# EVGP_Daugherboard_2.net
KiCad netlist of a schematic drawn in EAGLE
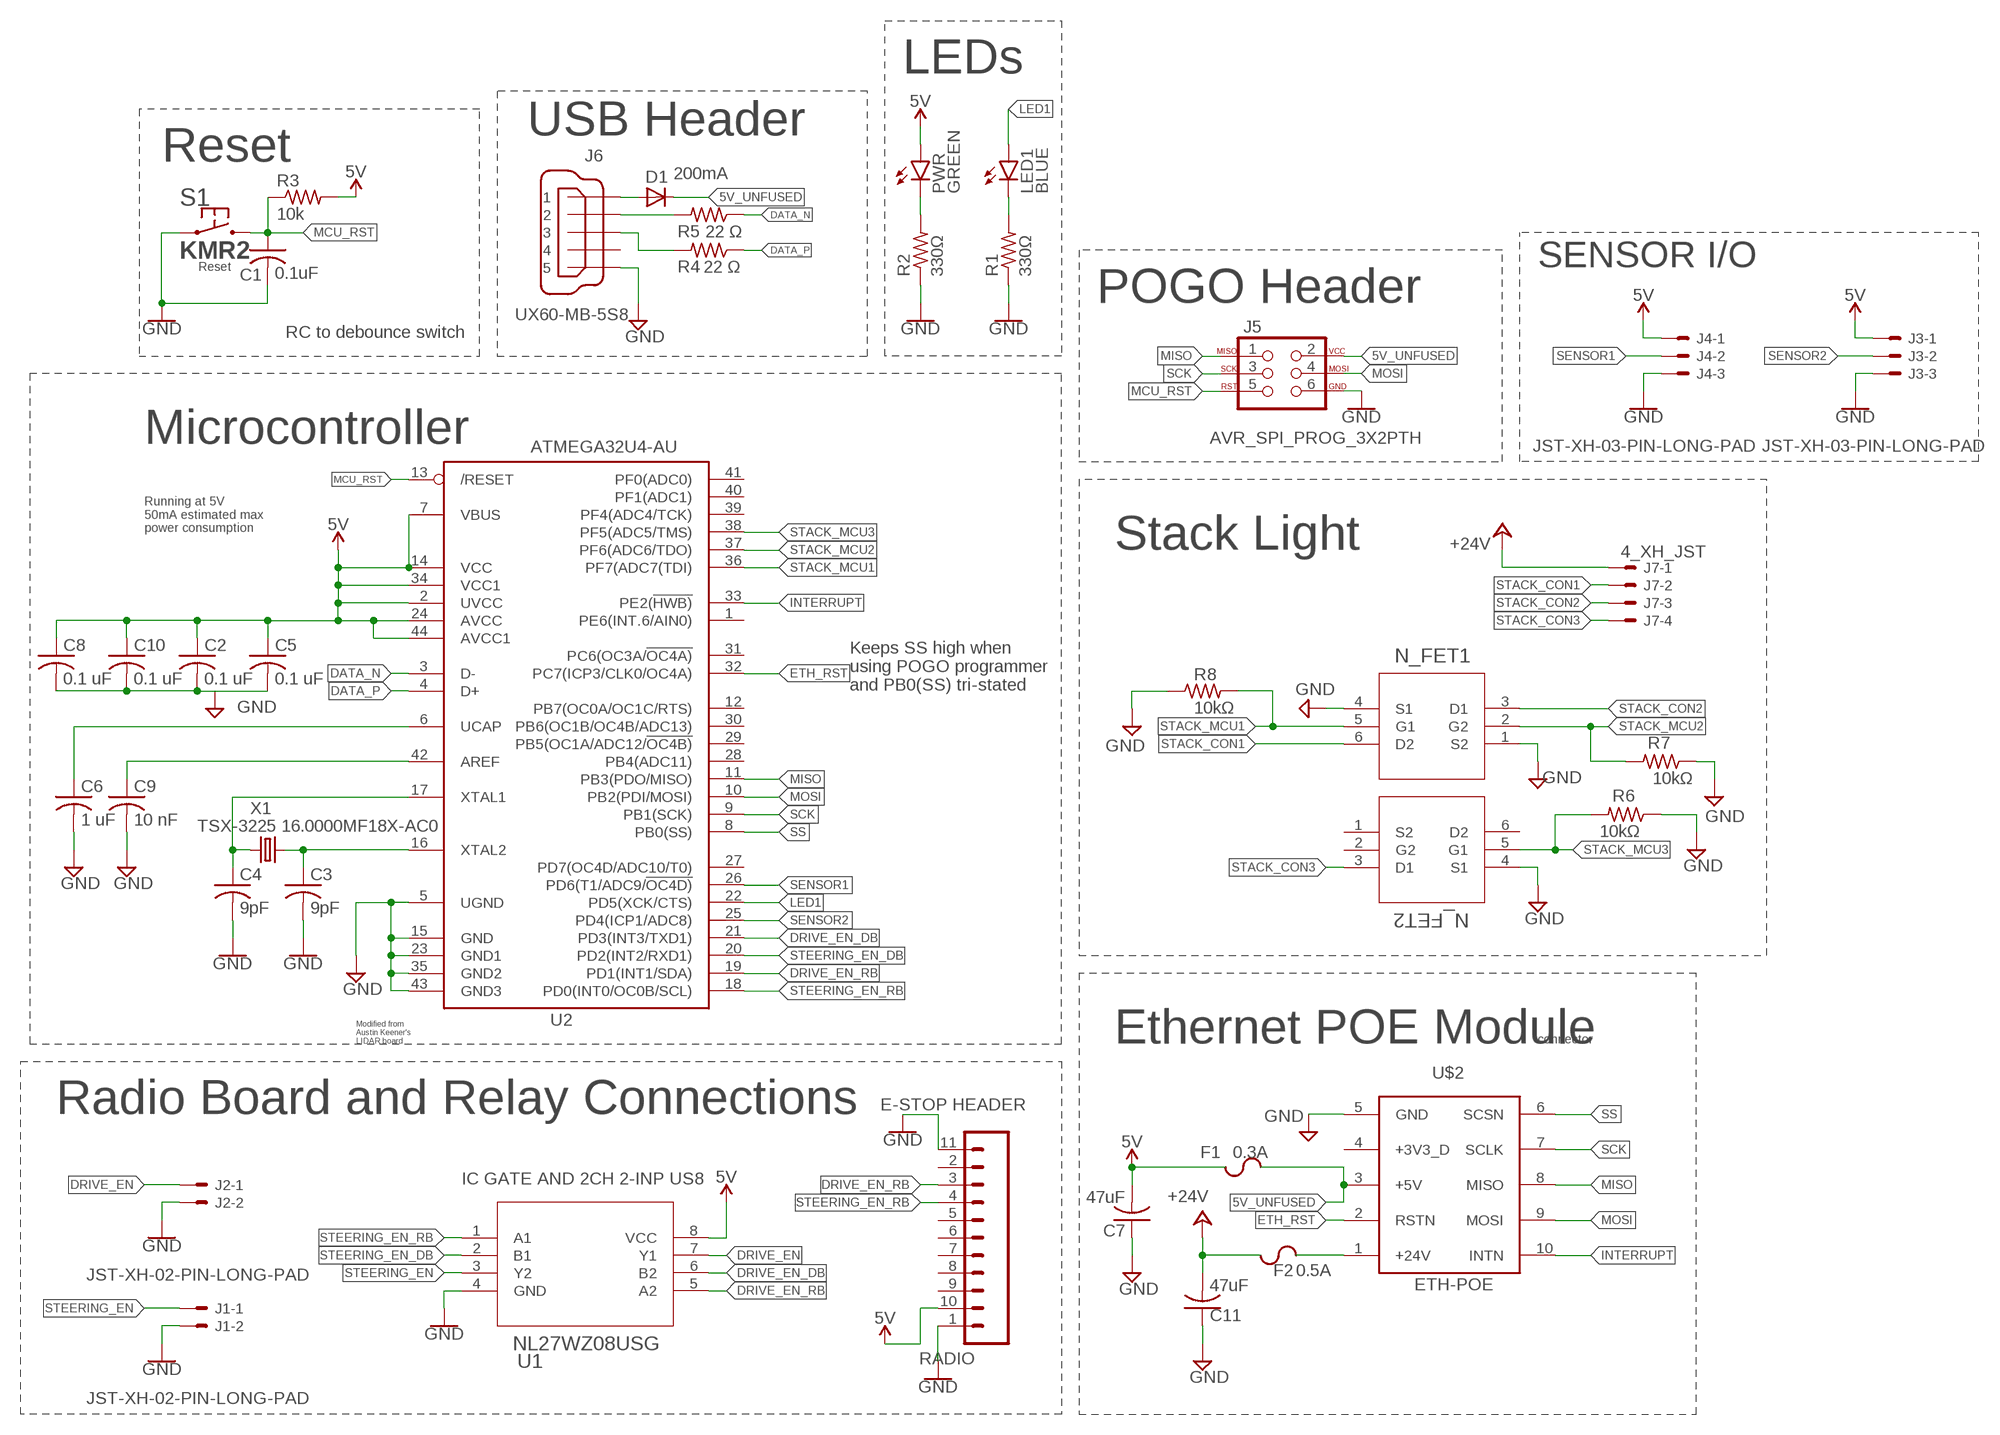
[diagram p0: schematic, sheet 1]

(export (version "E")
  (design (tool "Eeschema 10.0.6"))
  (components
    (comp (ref "C1")
      (value "0.1uF")
      (footprint "eagle-import:C0603")
      (libsource (lib "eagle-import") (part "C-USC0603"))
    )
    (comp (ref "C2")
      (value "0.1 uF")
      (footprint "eagle-import:C0603")
      (libsource (lib "eagle-import") (part "resistor_348_C-USC0603"))
    )
    (comp (ref "C3")
      (value "9pF")
      (footprint "eagle-import:C0603")
      (libsource (lib "eagle-import") (part "resistor_348_C-USC0603"))
    )
    (comp (ref "C4")
      (value "9pF")
      (footprint "eagle-import:C0603")
      (libsource (lib "eagle-import") (part "resistor_348_C-USC0603"))
    )
    (comp (ref "C5")
      (value "0.1 uF")
      (footprint "eagle-import:C0603")
      (libsource (lib "eagle-import") (part "resistor_348_C-USC0603"))
    )
    (comp (ref "C6")
      (value "1 uF")
      (footprint "eagle-import:C0603")
      (libsource (lib "eagle-import") (part "resistor_348_C-USC0603"))
    )
    (comp (ref "C7")
      (value "47uF")
      (footprint "eagle-import:C1206")
      (libsource (lib "eagle-import") (part "C-USC1206"))
    )
    (comp (ref "C8")
      (value "0.1 uF")
      (footprint "eagle-import:C0603")
      (libsource (lib "eagle-import") (part "resistor_348_C-USC0603"))
    )
    (comp (ref "C9")
      (value "10 nF")
      (footprint "eagle-import:C0603")
      (libsource (lib "eagle-import") (part "resistor_348_C-USC0603"))
    )
    (comp (ref "C10")
      (value "0.1 uF")
      (footprint "eagle-import:C0603")
      (libsource (lib "eagle-import") (part "resistor_348_C-USC0603"))
    )
    (comp (ref "C11")
      (value "47uF")
      (footprint "eagle-import:C1206")
      (libsource (lib "eagle-import") (part "C-USC1206"))
    )
    (comp (ref "D1")
      (value "200mA")
      (footprint "eagle-import:SOD323-R")
      (libsource (lib "eagle-import") (part "DIODE-SOD323-R"))
    )
    (comp (ref "F1")
      (value "0.3A")
      (footprint "eagle-import:F1206")
      (libsource (lib "eagle-import") (part "CHIP_FUSE1206"))
    )
    (comp (ref "F2")
      (value "0.5A")
      (footprint "eagle-import:F1206")
      (libsource (lib "eagle-import") (part "CHIP_FUSE1206"))
    )
    (comp (ref "J1")
      (value "JST-XH-02-PIN-LONG-PAD")
      (footprint "eagle-import:JST-XH-02-PACKAGE-LONG-PAD")
      (libsource (lib "eagle-import") (part "JST-XH-02-PIN-LONG-PAD"))
    )
    (comp (ref "J2")
      (value "JST-XH-02-PIN-LONG-PAD")
      (footprint "eagle-import:JST-XH-02-PACKAGE-LONG-PAD")
      (libsource (lib "eagle-import") (part "JST-XH-02-PIN-LONG-PAD"))
    )
    (comp (ref "J3")
      (value "JST-XH-03-PIN-LONG-PAD")
      (footprint "eagle-import:JST-XH-03-PACKAGE-LONG-PAD")
      (libsource (lib "eagle-import") (part "JST-XH-03-PIN-LONG-PAD"))
    )
    (comp (ref "J4")
      (value "JST-XH-03-PIN-LONG-PAD")
      (footprint "eagle-import:JST-XH-03-PACKAGE-LONG-PAD")
      (libsource (lib "eagle-import") (part "JST-XH-03-PIN-LONG-PAD"))
    )
    (comp (ref "J5")
      (value "AVR_SPI_PROG_3X2PTH")
      (footprint "eagle-import:2X3")
      (libsource (lib "eagle-import") (part "AVR_SPI_PROG_3X2PTH"))
    )
    (comp (ref "J6")
      (value "UX60-MB-5S8")
      (footprint "eagle-import:UX60-MB-5S8")
      (libsource (lib "eagle-import") (part "UX60-MB-5S?8"))
    )
    (comp (ref "J7")
      (value "4_XH_JST")
      (footprint "eagle-import:JST-XH-04-PACKAGE-LONG-PAD")
      (libsource (lib "eagle-import") (part "JST-XH-04-PIN-LONG-PAD"))
    )
    (comp (ref "LED1")
      (value "BLUE")
      (footprint "eagle-import:CHIP-LED0603")
      (libsource (lib "eagle-import") (part "LEDCHIP-LED0603"))
    )
    (comp (ref "PWR")
      (value "GREEN")
      (footprint "eagle-import:CHIP-LED0603")
      (libsource (lib "eagle-import") (part "LEDCHIP-LED0603"))
    )
    (comp (ref "Q1")
      (value "N_FET2")
      (footprint "eagle-import:SOT-363")
      (fields (field (name "MANUFACTURER_PART_NUMBER") "BSS84DW7F"))
      (libsource (lib "eagle-import") (part "BSS84DW-7-F"))
    )
    (comp (ref "Q2")
      (value "N_FET1")
      (footprint "eagle-import:SOT-363")
      (fields (field (name "MANUFACTURER_PART_NUMBER") "BSS84DW7F"))
      (libsource (lib "eagle-import") (part "BSS84DW-7-F"))
    )
    (comp (ref "R1")
      (value "330Ω")
      (footprint "eagle-import:R0603")
      (libsource (lib "eagle-import") (part "R-US_R0603"))
    )
    (comp (ref "R2")
      (value "330Ω")
      (footprint "eagle-import:R0603")
      (libsource (lib "eagle-import") (part "R-US_R0603"))
    )
    (comp (ref "R3")
      (value "10k")
      (footprint "eagle-import:R0603")
      (libsource (lib "eagle-import") (part "R-US_R0603"))
    )
    (comp (ref "R4")
      (value "22 Ω")
      (footprint "eagle-import:R0603")
      (libsource (lib "eagle-import") (part "R-US_R0603"))
    )
    (comp (ref "R5")
      (value "22 Ω")
      (footprint "eagle-import:R0603")
      (libsource (lib "eagle-import") (part "R-US_R0603"))
    )
    (comp (ref "R6")
      (value "10kΩ")
      (footprint "eagle-import:R0603")
      (libsource (lib "eagle-import") (part "R-US_R0603"))
    )
    (comp (ref "R7")
      (value "10kΩ")
      (footprint "eagle-import:R0603")
      (libsource (lib "eagle-import") (part "R-US_R0603"))
    )
    (comp (ref "R8")
      (value "10kΩ")
      (footprint "eagle-import:R0603")
      (libsource (lib "eagle-import") (part "R-US_R0603"))
    )
    (comp (ref "RADIO")
      (value "E-STOP HEADER")
      (footprint "eagle-import:RADIO_V1.3")
      (libsource (lib "eagle-import") (part "ESTOP_RADIO"))
    )
    (comp (ref "S1")
      (value "KMR2")
      (footprint "eagle-import:KMR2")
      (fields (field (name "FUNCTION") "Reset"))
      (libsource (lib "eagle-import") (part "KMR2"))
    )
    (comp (ref "U$2")
      (value "ETH-POE")
      (footprint "eagle-import:HDRVR10W64P4000X254_2X5_1016X508X254B")
      (libsource (lib "eagle-import") (part "ETH-POE"))
    )
    (comp (ref "U1")
      (value "NL27WZ08USG")
      (footprint "eagle-import:US8_2P40X2P10")
      (libsource (lib "eagle-import") (part "NL27WZ08USG"))
    )
    (comp (ref "U2")
      (value "ATMEGA32U4-AU")
      (footprint "eagle-import:TQFP44")
      (libsource (lib "eagle-import") (part "ATMEGA32U4-AU"))
    )
    (comp (ref "X1")
      (value "TSX-3225 16.0000MF18X-AC0")
      (footprint "eagle-import:XTAL-3.2X2.5")
      (libsource (lib "eagle-import") (part "XTAL-3.2X2.5"))
    )
  )
  (nets
    (net (code "1") (name "+24V") (class "Default")
      (node (ref "C11") (pin "2") (pinfunction "2_2") (pintype "passive"))
      (node (ref "F2") (pin "1") (pinfunction "1_1") (pintype "bidirectional"))
      (node (ref "J7") (pin "1") (pinfunction "S_1") (pintype "passive"))
    )
    (net (code "2") (name "5V") (class "Default")
      (node (ref "C10") (pin "1") (pinfunction "1_1") (pintype "passive"))
      (node (ref "C2") (pin "1") (pinfunction "1_1") (pintype "passive"))
      (node (ref "C5") (pin "1") (pinfunction "1_1") (pintype "passive"))
      (node (ref "C7") (pin "2") (pinfunction "2_2") (pintype "passive"))
      (node (ref "C8") (pin "1") (pinfunction "1_1") (pintype "passive"))
      (node (ref "F1") (pin "1") (pinfunction "1_1") (pintype "bidirectional"))
      (node (ref "J3") (pin "1") (pinfunction "S_1") (pintype "passive"))
      (node (ref "J4") (pin "1") (pinfunction "S_1") (pintype "passive"))
      (node (ref "PWR") (pin "A") (pinfunction "A_A") (pintype "passive"))
      (node (ref "R3") (pin "2") (pinfunction "2_2") (pintype "passive"))
      (node (ref "RADIO") (pin "10") (pinfunction "5V_10") (pintype "passive"))
      (node (ref "U1") (pin "8") (pinfunction "VCC_8") (pintype "power_in"))
      (node (ref "U2") (pin "14") (pinfunction "VCC_14") (pintype "bidirectional"))
      (node (ref "U2") (pin "2") (pinfunction "UVCC_2") (pintype "bidirectional"))
      (node (ref "U2") (pin "24") (pinfunction "AVCC_24") (pintype "bidirectional"))
      (node (ref "U2") (pin "34") (pinfunction "VCC1_34") (pintype "bidirectional"))
      (node (ref "U2") (pin "44") (pinfunction "AVCC1_44") (pintype "bidirectional"))
      (node (ref "U2") (pin "7") (pinfunction "VBUS_7") (pintype "bidirectional"))
    )
    (net (code "3") (name "5V_UNFUSED") (class "Default")
      (node (ref "D1") (pin "C") (pinfunction "C_C") (pintype "passive"))
      (node (ref "F1") (pin "2") (pinfunction "2_2") (pintype "bidirectional"))
      (node (ref "J5") (pin "2") (pinfunction "2_2") (pintype "passive"))
      (node (ref "U$2") (pin "3") (pinfunction "+5V_3") (pintype "bidirectional"))
    )
    (net (code "4") (name "DATA_N") (class "Default")
      (node (ref "R5") (pin "1") (pinfunction "1_1") (pintype "passive"))
      (node (ref "U2") (pin "3") (pinfunction "D-_3") (pintype "bidirectional"))
    )
    (net (code "5") (name "DATA_P") (class "Default")
      (node (ref "R4") (pin "1") (pinfunction "1_1") (pintype "passive"))
      (node (ref "U2") (pin "4") (pinfunction "D+_4") (pintype "bidirectional"))
    )
    (net (code "6") (name "DRIVE_EN") (class "Default")
      (node (ref "J2") (pin "1") (pinfunction "S_1") (pintype "passive"))
      (node (ref "U1") (pin "7") (pinfunction "Y1_7") (pintype "output"))
    )
    (net (code "7") (name "DRIVE_EN_DB") (class "Default")
      (node (ref "U1") (pin "6") (pinfunction "B2_6") (pintype "input"))
      (node (ref "U2") (pin "21") (pinfunction "PD3(INT3/TXD1)_21") (pintype "bidirectional"))
    )
    (net (code "8") (name "DRIVE_EN_RB") (class "Default")
      (node (ref "RADIO") (pin "3") (pinfunction "D1_3") (pintype "passive"))
      (node (ref "U1") (pin "5") (pinfunction "A2_5") (pintype "input"))
      (node (ref "U2") (pin "19") (pinfunction "PD1(INT1/SDA)_19") (pintype "bidirectional"))
    )
    (net (code "9") (name "ETH_RST") (class "Default")
      (node (ref "U$2") (pin "2") (pinfunction "RSTN_2") (pintype "bidirectional"))
      (node (ref "U2") (pin "32") (pinfunction "PC7(ICP3/CLK0/OC4A)_32") (pintype "bidirectional"))
    )
    (net (code "10") (name "GND") (class "Default")
      (node (ref "C1") (pin "2") (pinfunction "2_2") (pintype "passive"))
      (node (ref "C10") (pin "2") (pinfunction "2_2") (pintype "passive"))
      (node (ref "C11") (pin "1") (pinfunction "1_1") (pintype "passive"))
      (node (ref "C2") (pin "2") (pinfunction "2_2") (pintype "passive"))
      (node (ref "C3") (pin "2") (pinfunction "2_2") (pintype "passive"))
      (node (ref "C4") (pin "2") (pinfunction "2_2") (pintype "passive"))
      (node (ref "C5") (pin "2") (pinfunction "2_2") (pintype "passive"))
      (node (ref "C6") (pin "2") (pinfunction "2_2") (pintype "passive"))
      (node (ref "C7") (pin "1") (pinfunction "1_1") (pintype "passive"))
      (node (ref "C8") (pin "2") (pinfunction "2_2") (pintype "passive"))
      (node (ref "C9") (pin "2") (pinfunction "2_2") (pintype "passive"))
      (node (ref "J1") (pin "2") (pinfunction "S_2") (pintype "passive"))
      (node (ref "J2") (pin "2") (pinfunction "S_2") (pintype "passive"))
      (node (ref "J3") (pin "3") (pinfunction "S_3") (pintype "passive"))
      (node (ref "J4") (pin "3") (pinfunction "S_3") (pintype "passive"))
      (node (ref "J5") (pin "6") (pinfunction "6_6") (pintype "passive"))
      (node (ref "J6") (pin "5") (pinfunction "5_5") (pintype "passive"))
      (node (ref "Q1") (pin "4") (pinfunction "S1_4") (pintype "passive"))
      (node (ref "Q2") (pin "1") (pinfunction "S2_1") (pintype "passive"))
      (node (ref "Q2") (pin "4") (pinfunction "S1_4") (pintype "passive"))
      (node (ref "R1") (pin "1") (pinfunction "1_1") (pintype "passive"))
      (node (ref "R2") (pin "1") (pinfunction "1_1") (pintype "passive"))
      (node (ref "R6") (pin "1") (pinfunction "1_1") (pintype "passive"))
      (node (ref "R7") (pin "1") (pinfunction "1_1") (pintype "passive"))
      (node (ref "R8") (pin "1") (pinfunction "1_1") (pintype "passive"))
      (node (ref "RADIO") (pin "1") (pinfunction "GND_1") (pintype "passive"))
      (node (ref "RADIO") (pin "11") (pinfunction "GND_11") (pintype "passive"))
      (node (ref "S1") (pin "1.1") (pinfunction "1_1.1") (pintype "passive"))
      (node (ref "S1") (pin "1.2") (pinfunction "1_1.2") (pintype "passive"))
      (node (ref "U$2") (pin "5") (pinfunction "GND_5") (pintype "bidirectional"))
      (node (ref "U1") (pin "4") (pinfunction "GND_4") (pintype "power_in"))
      (node (ref "U2") (pin "15") (pinfunction "GND_15") (pintype "bidirectional"))
      (node (ref "U2") (pin "23") (pinfunction "GND1_23") (pintype "bidirectional"))
      (node (ref "U2") (pin "35") (pinfunction "GND2_35") (pintype "bidirectional"))
      (node (ref "U2") (pin "43") (pinfunction "GND3_43") (pintype "bidirectional"))
      (node (ref "U2") (pin "5") (pinfunction "UGND_5") (pintype "bidirectional"))
    )
    (net (code "11") (name "INTERRUPT") (class "Default")
      (node (ref "U$2") (pin "10") (pinfunction "INTN_10") (pintype "bidirectional"))
      (node (ref "U2") (pin "33") (pinfunction "PE2(~{HWB})_33") (pintype "bidirectional"))
    )
    (net (code "12") (name "LED1") (class "Default")
      (node (ref "LED1") (pin "A") (pinfunction "A_A") (pintype "passive"))
      (node (ref "U2") (pin "22") (pinfunction "PD5(XCK/CTS)_22") (pintype "bidirectional"))
    )
    (net (code "13") (name "MCU_RST") (class "Default")
      (node (ref "C1") (pin "1") (pinfunction "1_1") (pintype "passive"))
      (node (ref "J5") (pin "5") (pinfunction "5_5") (pintype "passive"))
      (node (ref "R3") (pin "1") (pinfunction "1_1") (pintype "passive"))
      (node (ref "S1") (pin "2.1") (pinfunction "2_2.1") (pintype "passive"))
      (node (ref "S1") (pin "2.2") (pinfunction "2_2.2") (pintype "passive"))
      (node (ref "U2") (pin "13") (pinfunction "/RESET_13") (pintype "bidirectional"))
    )
    (net (code "14") (name "MISO") (class "Default")
      (node (ref "J5") (pin "1") (pinfunction "1_1") (pintype "passive"))
      (node (ref "U$2") (pin "8") (pinfunction "MISO_8") (pintype "bidirectional"))
      (node (ref "U2") (pin "11") (pinfunction "PB3(PDO/MISO)_11") (pintype "bidirectional"))
    )
    (net (code "15") (name "MOSI") (class "Default")
      (node (ref "J5") (pin "4") (pinfunction "4_4") (pintype "passive"))
      (node (ref "U$2") (pin "9") (pinfunction "MOSI_9") (pintype "bidirectional"))
      (node (ref "U2") (pin "10") (pinfunction "PB2(PDI/MOSI)_10") (pintype "bidirectional"))
    )
    (net (code "16") (name "Net-(D1-PadA)") (class "Default")
      (node (ref "D1") (pin "A") (pinfunction "A_A") (pintype "passive"))
      (node (ref "J6") (pin "1") (pinfunction "1_1") (pintype "passive"))
    )
    (net (code "17") (name "Net-(J6-Pad2)") (class "Default")
      (node (ref "J6") (pin "2") (pinfunction "2_2") (pintype "passive"))
      (node (ref "R5") (pin "2") (pinfunction "2_2") (pintype "passive"))
    )
    (net (code "18") (name "Net-(J6-Pad3)") (class "Default")
      (node (ref "J6") (pin "3") (pinfunction "3_3") (pintype "passive"))
      (node (ref "R4") (pin "2") (pinfunction "2_2") (pintype "passive"))
    )
    (net (code "19") (name "Net-(LED1-PadC)") (class "Default")
      (node (ref "LED1") (pin "C") (pinfunction "C_C") (pintype "passive"))
      (node (ref "R1") (pin "2") (pinfunction "2_2") (pintype "passive"))
    )
    (net (code "20") (name "Net-(PWR-PadC)") (class "Default")
      (node (ref "PWR") (pin "C") (pinfunction "C_C") (pintype "passive"))
      (node (ref "R2") (pin "2") (pinfunction "2_2") (pintype "passive"))
    )
    (net (code "21") (name "Net-(U$2-+24V)") (class "Default")
      (node (ref "F2") (pin "2") (pinfunction "2_2") (pintype "bidirectional"))
      (node (ref "U$2") (pin "1") (pinfunction "+24V_1") (pintype "bidirectional"))
    )
    (net (code "22") (name "Net-(U2-AREF)") (class "Default")
      (node (ref "C9") (pin "1") (pinfunction "1_1") (pintype "passive"))
      (node (ref "U2") (pin "42") (pinfunction "AREF_42") (pintype "bidirectional"))
    )
    (net (code "23") (name "Net-(U2-UCAP)") (class "Default")
      (node (ref "C6") (pin "1") (pinfunction "1_1") (pintype "passive"))
      (node (ref "U2") (pin "6") (pinfunction "UCAP_6") (pintype "bidirectional"))
    )
    (net (code "24") (name "Net-(U2-XTAL1)") (class "Default")
      (node (ref "C4") (pin "1") (pinfunction "1_1") (pintype "passive"))
      (node (ref "U2") (pin "17") (pinfunction "XTAL1_17") (pintype "bidirectional"))
      (node (ref "X1") (pin "1") (pinfunction "1_1") (pintype "passive"))
    )
    (net (code "25") (name "Net-(U2-XTAL2)") (class "Default")
      (node (ref "C3") (pin "1") (pinfunction "1_1") (pintype "passive"))
      (node (ref "U2") (pin "16") (pinfunction "XTAL2_16") (pintype "bidirectional"))
      (node (ref "X1") (pin "3") (pinfunction "2_3") (pintype "passive"))
    )
    (net (code "26") (name "SCK") (class "Default")
      (node (ref "J5") (pin "3") (pinfunction "3_3") (pintype "passive"))
      (node (ref "U$2") (pin "7") (pinfunction "SCLK_7") (pintype "bidirectional"))
      (node (ref "U2") (pin "9") (pinfunction "PB1(SCK)_9") (pintype "bidirectional"))
    )
    (net (code "27") (name "SENSOR1") (class "Default")
      (node (ref "J4") (pin "2") (pinfunction "S_2") (pintype "passive"))
      (node (ref "U2") (pin "26") (pinfunction "PD6(T1/ADC9/~{OC4D})_26") (pintype "bidirectional"))
    )
    (net (code "28") (name "SENSOR2") (class "Default")
      (node (ref "J3") (pin "2") (pinfunction "S_2") (pintype "passive"))
      (node (ref "U2") (pin "25") (pinfunction "PD4(ICP1/ADC8)_25") (pintype "bidirectional"))
    )
    (net (code "29") (name "SS") (class "Default")
      (node (ref "U$2") (pin "6") (pinfunction "SCSN_6") (pintype "bidirectional"))
      (node (ref "U2") (pin "8") (pinfunction "PB0(SS)_8") (pintype "bidirectional"))
    )
    (net (code "30") (name "STACK_CON1") (class "Default")
      (node (ref "J7") (pin "2") (pinfunction "S_2") (pintype "passive"))
      (node (ref "Q2") (pin "6") (pinfunction "D2_6") (pintype "passive"))
    )
    (net (code "31") (name "STACK_CON2") (class "Default")
      (node (ref "J7") (pin "3") (pinfunction "S_3") (pintype "passive"))
      (node (ref "Q2") (pin "3") (pinfunction "D1_3") (pintype "passive"))
    )
    (net (code "32") (name "STACK_CON3") (class "Default")
      (node (ref "J7") (pin "4") (pinfunction "S_4") (pintype "passive"))
      (node (ref "Q1") (pin "3") (pinfunction "D1_3") (pintype "passive"))
    )
    (net (code "33") (name "STACK_MCU1") (class "Default")
      (node (ref "Q2") (pin "5") (pinfunction "G1_5") (pintype "passive"))
      (node (ref "R8") (pin "2") (pinfunction "2_2") (pintype "passive"))
      (node (ref "U2") (pin "36") (pinfunction "PF7(ADC7(TDI)_36") (pintype "bidirectional"))
    )
    (net (code "34") (name "STACK_MCU2") (class "Default")
      (node (ref "Q2") (pin "2") (pinfunction "G2_2") (pintype "passive"))
      (node (ref "R7") (pin "2") (pinfunction "2_2") (pintype "passive"))
      (node (ref "U2") (pin "37") (pinfunction "PF6(ADC6/TDO)_37") (pintype "bidirectional"))
    )
    (net (code "35") (name "STACK_MCU3") (class "Default")
      (node (ref "Q1") (pin "5") (pinfunction "G1_5") (pintype "passive"))
      (node (ref "R6") (pin "2") (pinfunction "2_2") (pintype "passive"))
      (node (ref "U2") (pin "38") (pinfunction "PF5(ADC5/TMS)_38") (pintype "bidirectional"))
    )
    (net (code "36") (name "STEERING_EN") (class "Default")
      (node (ref "J1") (pin "1") (pinfunction "S_1") (pintype "passive"))
      (node (ref "U1") (pin "3") (pinfunction "Y2_3") (pintype "output"))
    )
    (net (code "37") (name "STEERING_EN_DB") (class "Default")
      (node (ref "U1") (pin "2") (pinfunction "B1_2") (pintype "input"))
      (node (ref "U2") (pin "20") (pinfunction "PD2(INT2/RXD1)_20") (pintype "bidirectional"))
    )
    (net (code "38") (name "STEERING_EN_RB") (class "Default")
      (node (ref "RADIO") (pin "4") (pinfunction "D2_4") (pintype "passive"))
      (node (ref "U1") (pin "1") (pinfunction "A1_1") (pintype "input"))
      (node (ref "U2") (pin "18") (pinfunction "PD0(INT0/OC0B/SCL)_18") (pintype "bidirectional"))
    )
    (net (code "39") (name "unconnected-(J6-Pad4)") (class "Default")
      (node (ref "J6") (pin "4") (pinfunction "4_4") (pintype "passive"))
    )
    (net (code "40") (name "unconnected-(Q1-D2-Pad6)") (class "Default")
      (node (ref "Q1") (pin "6") (pinfunction "D2_6") (pintype "passive"))
    )
    (net (code "41") (name "unconnected-(Q1-G2-Pad2)") (class "Default")
      (node (ref "Q1") (pin "2") (pinfunction "G2_2") (pintype "passive"))
    )
    (net (code "42") (name "unconnected-(Q1-S2-Pad1)") (class "Default")
      (node (ref "Q1") (pin "1") (pinfunction "S2_1") (pintype "passive"))
    )
    (net (code "43") (name "unconnected-(RADIO-D3-Pad5)") (class "Default")
      (node (ref "RADIO") (pin "5") (pinfunction "D3_5") (pintype "passive"))
    )
    (net (code "44") (name "unconnected-(RADIO-D4-Pad6)") (class "Default")
      (node (ref "RADIO") (pin "6") (pinfunction "D4_6") (pintype "passive"))
    )
    (net (code "45") (name "unconnected-(RADIO-D5-Pad7)") (class "Default")
      (node (ref "RADIO") (pin "7") (pinfunction "D5_7") (pintype "passive"))
    )
    (net (code "46") (name "unconnected-(RADIO-D6-Pad8)") (class "Default")
      (node (ref "RADIO") (pin "8") (pinfunction "D6_8") (pintype "passive"))
    )
    (net (code "47") (name "unconnected-(RADIO-D7-Pad9)") (class "Default")
      (node (ref "RADIO") (pin "9") (pinfunction "D7_9") (pintype "passive"))
    )
    (net (code "48") (name "unconnected-(RADIO-RST-Pad2)") (class "Default")
      (node (ref "RADIO") (pin "2") (pinfunction "RST_2") (pintype "passive"))
    )
    (net (code "49") (name "unconnected-(U$2-+3V3_D-Pad4)") (class "Default")
      (node (ref "U$2") (pin "4") (pinfunction "+3V3_D_4") (pintype "bidirectional"))
    )
    (net (code "50") (name "unconnected-(U2-PB4(ADC11)-Pad28)") (class "Default")
      (node (ref "U2") (pin "28") (pinfunction "PB4(ADC11)_28") (pintype "bidirectional"))
    )
    (net (code "51") (name "unconnected-(U2-PB5(OC1A{slash}ADC12{slash}~{OC4B})-Pad29)") (class "Default")
      (node (ref "U2") (pin "29") (pinfunction "PB5(OC1A/ADC12/~{OC4B})_29") (pintype "bidirectional"))
    )
    (net (code "52") (name "unconnected-(U2-PB6(OC1B{slash}OC4B{slash}ADC13)-Pad30)") (class "Default")
      (node (ref "U2") (pin "30") (pinfunction "PB6(OC1B/OC4B/ADC13)_30") (pintype "bidirectional"))
    )
    (net (code "53") (name "unconnected-(U2-PB7(OC0A{slash}OC1C{slash}RTS)-Pad12)") (class "Default")
      (node (ref "U2") (pin "12") (pinfunction "PB7(OC0A/OC1C/RTS)_12") (pintype "bidirectional"))
    )
    (net (code "54") (name "unconnected-(U2-PC6(OC3A{slash}~{OC4A})-Pad31)") (class "Default")
      (node (ref "U2") (pin "31") (pinfunction "PC6(OC3A/~{OC4A})_31") (pintype "bidirectional"))
    )
    (net (code "55") (name "unconnected-(U2-PD7(OC4D{slash}ADC10{slash}T0)-Pad27)") (class "Default")
      (node (ref "U2") (pin "27") (pinfunction "PD7(OC4D/ADC10/T0)_27") (pintype "bidirectional"))
    )
    (net (code "56") (name "unconnected-(U2-PE6(INT.6{slash}AIN0)-Pad1)") (class "Default")
      (node (ref "U2") (pin "1") (pinfunction "PE6(INT.6/AIN0)_1") (pintype "bidirectional"))
    )
    (net (code "57") (name "unconnected-(U2-PF0(ADC0)-Pad41)") (class "Default")
      (node (ref "U2") (pin "41") (pinfunction "PF0(ADC0)_41") (pintype "bidirectional"))
    )
    (net (code "58") (name "unconnected-(U2-PF1(ADC1)-Pad40)") (class "Default")
      (node (ref "U2") (pin "40") (pinfunction "PF1(ADC1)_40") (pintype "bidirectional"))
    )
    (net (code "59") (name "unconnected-(U2-PF4(ADC4{slash}TCK)-Pad39)") (class "Default")
      (node (ref "U2") (pin "39") (pinfunction "PF4(ADC4/TCK)_39") (pintype "bidirectional"))
    )
  )
)
